# 1-Schematic_BLE_WAVER_DONGLE.net
KiCad netlist of a schematic drawn in EasyEDA
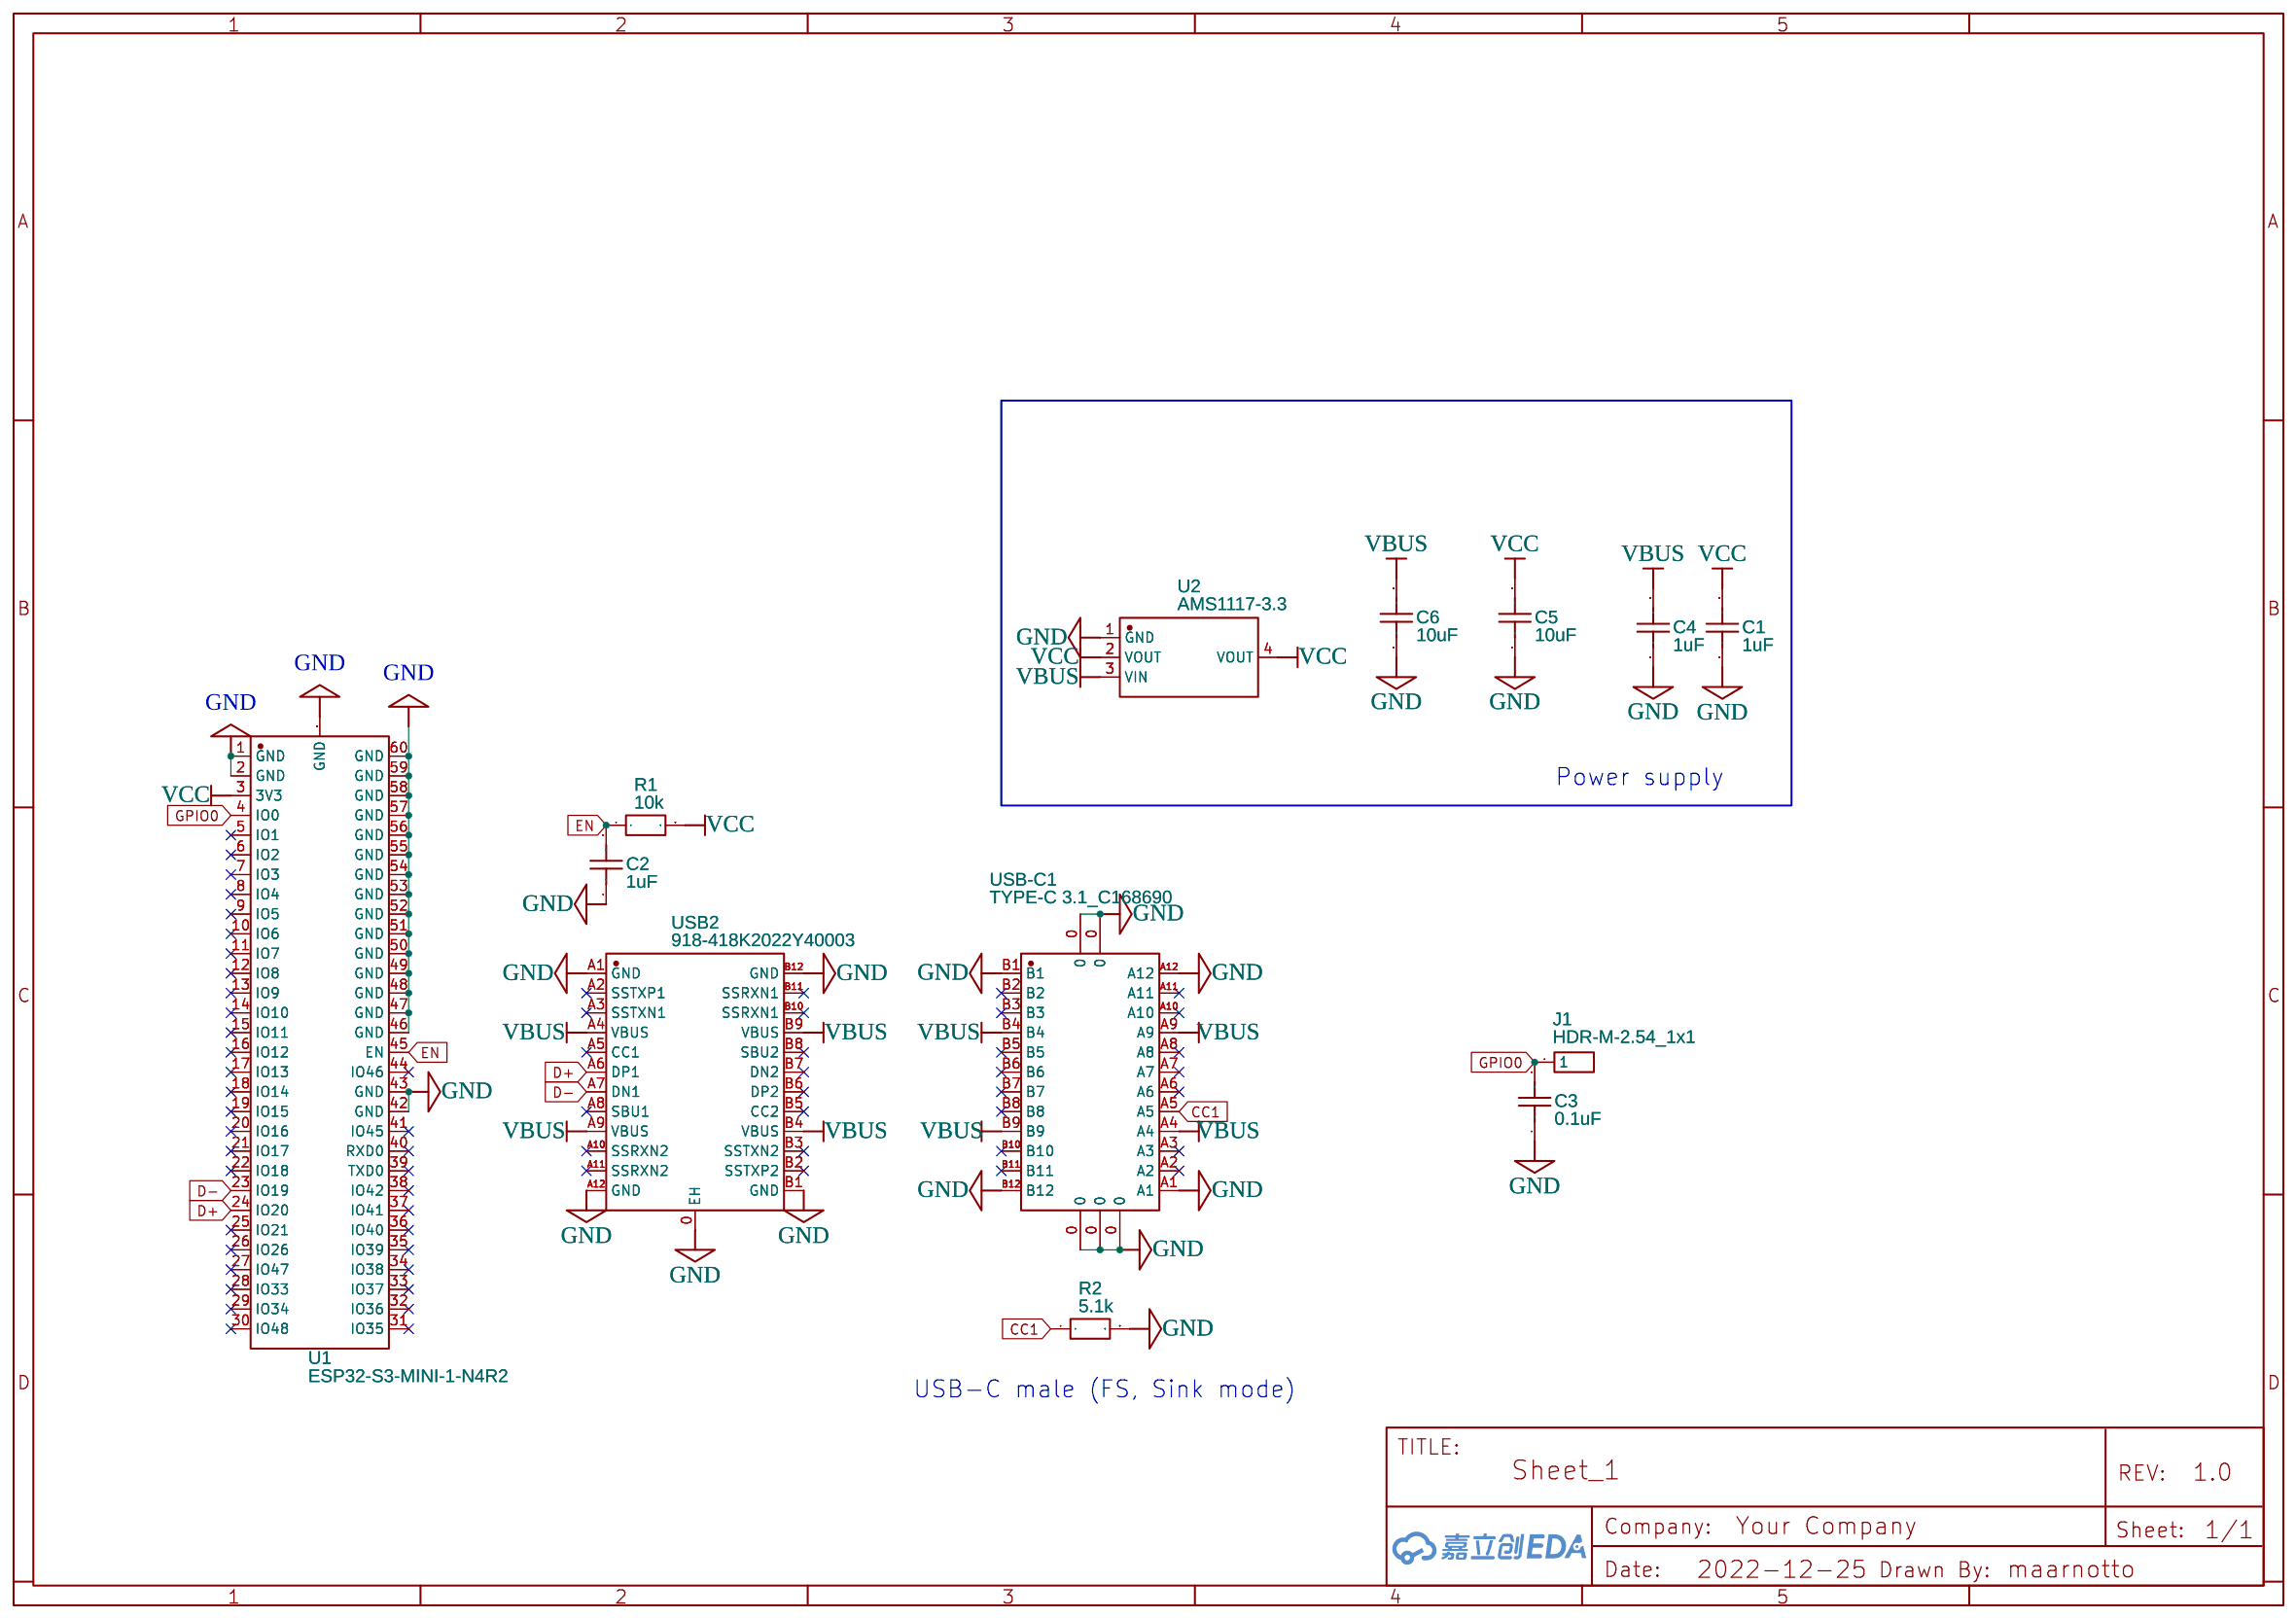
[diagram p0: schematic sheet]

(export (version "E")
  (design (tool "Eeschema 10.0.6"))
  (components
    (comp (ref "C1") (value "1uF") (libsource (lib "") (part "C_0603_US")))
    (comp (ref "C2") (value "1uF") (libsource (lib "") (part "C_0603_US")))
    (comp (ref "C3") (value "0.1uF") (libsource (lib "") (part "C_0603_US")))
    (comp (ref "C4") (value "1uF") (libsource (lib "") (part "C_0603_US")))
    (comp (ref "C5") (value "10uF") (libsource (lib "") (part "C_0603_US")))
    (comp (ref "C6") (value "10uF") (libsource (lib "") (part "C_0603_US")))
    (comp (ref "J1") (value "HDR-M-2.54_1x1") (libsource (lib "") (part "HDR-M-2.54_1x1")))
    (comp (ref "R1") (value "10k") (libsource (lib "") (part "R_0603_EU")))
    (comp (ref "R2") (value "5.1k") (libsource (lib "") (part "R_0603_EU")))
    (comp (ref "U1")
      (value "ESP32-S3-MINI-1-N4R2")
      (fields (field (name "Manufacturer") "ESPRESSIF(乐鑫)"))
      (libsource (lib "") (part "ESP32-S3-MINI-1-N4R2"))
    )
    (comp (ref "U2")
      (value "AMS1117-3.3")
      (fields (field (name "Manufacturer") "AMS"))
      (libsource (lib "") (part "AMS1117-3.3"))
    )
    (comp (ref "USB-C1")
      (value "TYPE-C 3.1_C168690")
      (fields (field (name "Manufacturer Part") "918-118A2021Y40000") (field (name "Manufacturer") "精拓金"))
      (libsource (lib "") (part "TYPE-C 3.1_C168690"))
    )
    (comp (ref "USB2")
      (value "918-418K2022Y40003")
      (fields (field (name "Manufacturer") "精拓金"))
      (libsource (lib "") (part "918-418K2022Y40003"))
    )
  )
  (nets
    (net (code "1") (name "CC1") (class "Default")
      (node (ref "R2") (pin "1") (pinfunction "1_1") (pintype "unspecified"))
      (node (ref "USB-C1") (pin "A5") (pinfunction "A5_A5") (pintype "unspecified"))
    )
    (net (code "2") (name "D+") (class "Default")
      (node (ref "U1") (pin "24") (pinfunction "IO20_24") (pintype "unspecified"))
      (node (ref "USB2") (pin "A6") (pinfunction "DP1_A6") (pintype "unspecified"))
    )
    (net (code "3") (name "D-") (class "Default")
      (node (ref "U1") (pin "23") (pinfunction "IO19_23") (pintype "unspecified"))
      (node (ref "USB2") (pin "A7") (pinfunction "DN1_A7") (pintype "unspecified"))
    )
    (net (code "4") (name "EN") (class "Default")
      (node (ref "C2") (pin "2") (pinfunction "2_2") (pintype "unspecified"))
      (node (ref "R1") (pin "1") (pinfunction "1_1") (pintype "unspecified"))
      (node (ref "U1") (pin "45") (pinfunction "EN_45") (pintype "unspecified"))
    )
    (net (code "5") (name "GND") (class "Default")
      (node (ref "C1") (pin "1") (pinfunction "1_1") (pintype "unspecified"))
      (node (ref "C2") (pin "1") (pinfunction "1_1") (pintype "unspecified"))
      (node (ref "C3") (pin "1") (pinfunction "1_1") (pintype "unspecified"))
      (node (ref "C4") (pin "1") (pinfunction "1_1") (pintype "unspecified"))
      (node (ref "C5") (pin "1") (pinfunction "1_1") (pintype "unspecified"))
      (node (ref "C6") (pin "1") (pinfunction "1_1") (pintype "unspecified"))
      (node (ref "R2") (pin "2") (pinfunction "2_2") (pintype "unspecified"))
      (node (ref "U1") (pin "1") (pinfunction "GND_1") (pintype "unspecified"))
      (node (ref "U1") (pin "2") (pinfunction "GND_2") (pintype "unspecified"))
      (node (ref "U1") (pin "42") (pinfunction "GND_42") (pintype "unspecified"))
      (node (ref "U1") (pin "43") (pinfunction "GND_43") (pintype "unspecified"))
      (node (ref "U1") (pin "46") (pinfunction "GND_46") (pintype "unspecified"))
      (node (ref "U1") (pin "47") (pinfunction "GND_47") (pintype "unspecified"))
      (node (ref "U1") (pin "48") (pinfunction "GND_48") (pintype "unspecified"))
      (node (ref "U1") (pin "49") (pinfunction "GND_49") (pintype "unspecified"))
      (node (ref "U1") (pin "50") (pinfunction "GND_50") (pintype "unspecified"))
      (node (ref "U1") (pin "51") (pinfunction "GND_51") (pintype "unspecified"))
      (node (ref "U1") (pin "52") (pinfunction "GND_52") (pintype "unspecified"))
      (node (ref "U1") (pin "53") (pinfunction "GND_53") (pintype "unspecified"))
      (node (ref "U1") (pin "54") (pinfunction "GND_54") (pintype "unspecified"))
      (node (ref "U1") (pin "55") (pinfunction "GND_55") (pintype "unspecified"))
      (node (ref "U1") (pin "56") (pinfunction "GND_56") (pintype "unspecified"))
      (node (ref "U1") (pin "57") (pinfunction "GND_57") (pintype "unspecified"))
      (node (ref "U1") (pin "58") (pinfunction "GND_58") (pintype "unspecified"))
      (node (ref "U1") (pin "59") (pinfunction "GND_59") (pintype "unspecified"))
      (node (ref "U1") (pin "60") (pinfunction "GND_60") (pintype "unspecified"))
      (node (ref "U1") (pin "GND") (pinfunction "GND_GND") (pintype "unspecified"))
      (node (ref "U2") (pin "1") (pinfunction "GND_1") (pintype "unspecified"))
      (node (ref "USB-C1") (pin "0") (pinfunction "0_0") (pintype "unspecified"))
      (node (ref "USB-C1") (pin "A1") (pinfunction "A1_A1") (pintype "unspecified"))
      (node (ref "USB-C1") (pin "A12") (pinfunction "A12_A12") (pintype "unspecified"))
      (node (ref "USB-C1") (pin "B1") (pinfunction "B1_B1") (pintype "unspecified"))
      (node (ref "USB-C1") (pin "B12") (pinfunction "B12_B12") (pintype "unspecified"))
      (node (ref "USB2") (pin "0") (pinfunction "EH_0") (pintype "unspecified"))
      (node (ref "USB2") (pin "A1") (pinfunction "GND_A1") (pintype "unspecified"))
      (node (ref "USB2") (pin "A12") (pinfunction "GND_A12") (pintype "unspecified"))
      (node (ref "USB2") (pin "B1") (pinfunction "GND_B1") (pintype "unspecified"))
      (node (ref "USB2") (pin "B12") (pinfunction "GND_B12") (pintype "unspecified"))
    )
    (net (code "6") (name "GPIO0") (class "Default")
      (node (ref "C3") (pin "2") (pinfunction "2_2") (pintype "unspecified"))
      (node (ref "J1") (pin "1") (pinfunction "1_1") (pintype "input"))
      (node (ref "U1") (pin "4") (pinfunction "IO0_4") (pintype "unspecified"))
    )
    (net (code "7") (name "VBUS") (class "Default")
      (node (ref "C4") (pin "2") (pinfunction "2_2") (pintype "unspecified"))
      (node (ref "C6") (pin "2") (pinfunction "2_2") (pintype "unspecified"))
      (node (ref "U2") (pin "3") (pinfunction "VIN_3") (pintype "unspecified"))
      (node (ref "USB-C1") (pin "A4") (pinfunction "A4_A4") (pintype "unspecified"))
      (node (ref "USB-C1") (pin "A9") (pinfunction "A9_A9") (pintype "unspecified"))
      (node (ref "USB-C1") (pin "B4") (pinfunction "B4_B4") (pintype "unspecified"))
      (node (ref "USB-C1") (pin "B9") (pinfunction "B9_B9") (pintype "unspecified"))
      (node (ref "USB2") (pin "A4") (pinfunction "VBUS_A4") (pintype "unspecified"))
      (node (ref "USB2") (pin "A9") (pinfunction "VBUS_A9") (pintype "unspecified"))
      (node (ref "USB2") (pin "B4") (pinfunction "VBUS_B4") (pintype "unspecified"))
      (node (ref "USB2") (pin "B9") (pinfunction "VBUS_B9") (pintype "unspecified"))
    )
    (net (code "8") (name "VCC") (class "Default")
      (node (ref "C1") (pin "2") (pinfunction "2_2") (pintype "unspecified"))
      (node (ref "C5") (pin "2") (pinfunction "2_2") (pintype "unspecified"))
      (node (ref "R1") (pin "2") (pinfunction "2_2") (pintype "unspecified"))
      (node (ref "U1") (pin "3") (pinfunction "3V3_3") (pintype "unspecified"))
      (node (ref "U2") (pin "2") (pinfunction "VOUT_2") (pintype "unspecified"))
      (node (ref "U2") (pin "4") (pinfunction "VOUT_4") (pintype "unspecified"))
    )
    (net (code "9") (name "unconnected-(U1-IO1-Pad5)") (class "Default")
      (node (ref "U1") (pin "5") (pinfunction "IO1_5") (pintype "unspecified+no_connect"))
    )
    (net (code "10") (name "unconnected-(U1-IO2-Pad6)") (class "Default")
      (node (ref "U1") (pin "6") (pinfunction "IO2_6") (pintype "unspecified+no_connect"))
    )
    (net (code "11") (name "unconnected-(U1-IO3-Pad7)") (class "Default")
      (node (ref "U1") (pin "7") (pinfunction "IO3_7") (pintype "unspecified+no_connect"))
    )
    (net (code "12") (name "unconnected-(U1-IO4-Pad8)") (class "Default")
      (node (ref "U1") (pin "8") (pinfunction "IO4_8") (pintype "unspecified+no_connect"))
    )
    (net (code "13") (name "unconnected-(U1-IO5-Pad9)") (class "Default")
      (node (ref "U1") (pin "9") (pinfunction "IO5_9") (pintype "unspecified+no_connect"))
    )
    (net (code "14") (name "unconnected-(U1-IO6-Pad10)") (class "Default")
      (node (ref "U1") (pin "10") (pinfunction "IO6_10") (pintype "unspecified+no_connect"))
    )
    (net (code "15") (name "unconnected-(U1-IO7-Pad11)") (class "Default")
      (node (ref "U1") (pin "11") (pinfunction "IO7_11") (pintype "unspecified+no_connect"))
    )
    (net (code "16") (name "unconnected-(U1-IO8-Pad12)") (class "Default")
      (node (ref "U1") (pin "12") (pinfunction "IO8_12") (pintype "unspecified+no_connect"))
    )
    (net (code "17") (name "unconnected-(U1-IO9-Pad13)") (class "Default")
      (node (ref "U1") (pin "13") (pinfunction "IO9_13") (pintype "unspecified+no_connect"))
    )
    (net (code "18") (name "unconnected-(U1-IO10-Pad14)") (class "Default")
      (node (ref "U1") (pin "14") (pinfunction "IO10_14") (pintype "unspecified+no_connect"))
    )
    (net (code "19") (name "unconnected-(U1-IO11-Pad15)") (class "Default")
      (node (ref "U1") (pin "15") (pinfunction "IO11_15") (pintype "unspecified+no_connect"))
    )
    (net (code "20") (name "unconnected-(U1-IO12-Pad16)") (class "Default")
      (node (ref "U1") (pin "16") (pinfunction "IO12_16") (pintype "unspecified+no_connect"))
    )
    (net (code "21") (name "unconnected-(U1-IO13-Pad17)") (class "Default")
      (node (ref "U1") (pin "17") (pinfunction "IO13_17") (pintype "unspecified+no_connect"))
    )
    (net (code "22") (name "unconnected-(U1-IO14-Pad18)") (class "Default")
      (node (ref "U1") (pin "18") (pinfunction "IO14_18") (pintype "unspecified+no_connect"))
    )
    (net (code "23") (name "unconnected-(U1-IO15-Pad19)") (class "Default")
      (node (ref "U1") (pin "19") (pinfunction "IO15_19") (pintype "unspecified+no_connect"))
    )
    (net (code "24") (name "unconnected-(U1-IO16-Pad20)") (class "Default")
      (node (ref "U1") (pin "20") (pinfunction "IO16_20") (pintype "unspecified+no_connect"))
    )
    (net (code "25") (name "unconnected-(U1-IO17-Pad21)") (class "Default")
      (node (ref "U1") (pin "21") (pinfunction "IO17_21") (pintype "unspecified+no_connect"))
    )
    (net (code "26") (name "unconnected-(U1-IO18-Pad22)") (class "Default")
      (node (ref "U1") (pin "22") (pinfunction "IO18_22") (pintype "unspecified+no_connect"))
    )
    (net (code "27") (name "unconnected-(U1-IO21-Pad25)") (class "Default")
      (node (ref "U1") (pin "25") (pinfunction "IO21_25") (pintype "unspecified+no_connect"))
    )
    (net (code "28") (name "unconnected-(U1-IO26-Pad26)") (class "Default")
      (node (ref "U1") (pin "26") (pinfunction "IO26_26") (pintype "unspecified+no_connect"))
    )
    (net (code "29") (name "unconnected-(U1-IO33-Pad28)") (class "Default")
      (node (ref "U1") (pin "28") (pinfunction "IO33_28") (pintype "unspecified+no_connect"))
    )
    (net (code "30") (name "unconnected-(U1-IO34-Pad29)") (class "Default")
      (node (ref "U1") (pin "29") (pinfunction "IO34_29") (pintype "unspecified+no_connect"))
    )
    (net (code "31") (name "unconnected-(U1-IO35-Pad31)") (class "Default")
      (node (ref "U1") (pin "31") (pinfunction "IO35_31") (pintype "unspecified+no_connect"))
    )
    (net (code "32") (name "unconnected-(U1-IO36-Pad32)") (class "Default")
      (node (ref "U1") (pin "32") (pinfunction "IO36_32") (pintype "unspecified+no_connect"))
    )
    (net (code "33") (name "unconnected-(U1-IO37-Pad33)") (class "Default")
      (node (ref "U1") (pin "33") (pinfunction "IO37_33") (pintype "unspecified+no_connect"))
    )
    (net (code "34") (name "unconnected-(U1-IO38-Pad34)") (class "Default")
      (node (ref "U1") (pin "34") (pinfunction "IO38_34") (pintype "unspecified+no_connect"))
    )
    (net (code "35") (name "unconnected-(U1-IO39-Pad35)") (class "Default")
      (node (ref "U1") (pin "35") (pinfunction "IO39_35") (pintype "unspecified+no_connect"))
    )
    (net (code "36") (name "unconnected-(U1-IO40-Pad36)") (class "Default")
      (node (ref "U1") (pin "36") (pinfunction "IO40_36") (pintype "unspecified+no_connect"))
    )
    (net (code "37") (name "unconnected-(U1-IO41-Pad37)") (class "Default")
      (node (ref "U1") (pin "37") (pinfunction "IO41_37") (pintype "unspecified+no_connect"))
    )
    (net (code "38") (name "unconnected-(U1-IO42-Pad38)") (class "Default")
      (node (ref "U1") (pin "38") (pinfunction "IO42_38") (pintype "unspecified+no_connect"))
    )
    (net (code "39") (name "unconnected-(U1-IO45-Pad41)") (class "Default")
      (node (ref "U1") (pin "41") (pinfunction "IO45_41") (pintype "unspecified+no_connect"))
    )
    (net (code "40") (name "unconnected-(U1-IO46-Pad44)") (class "Default")
      (node (ref "U1") (pin "44") (pinfunction "IO46_44") (pintype "unspecified+no_connect"))
    )
    (net (code "41") (name "unconnected-(U1-IO47-Pad27)") (class "Default")
      (node (ref "U1") (pin "27") (pinfunction "IO47_27") (pintype "unspecified+no_connect"))
    )
    (net (code "42") (name "unconnected-(U1-IO48-Pad30)") (class "Default")
      (node (ref "U1") (pin "30") (pinfunction "IO48_30") (pintype "unspecified+no_connect"))
    )
    (net (code "43") (name "unconnected-(U1-RXD0-Pad40)") (class "Default")
      (node (ref "U1") (pin "40") (pinfunction "RXD0_40") (pintype "unspecified+no_connect"))
    )
    (net (code "44") (name "unconnected-(U1-TXD0-Pad39)") (class "Default")
      (node (ref "U1") (pin "39") (pinfunction "TXD0_39") (pintype "unspecified+no_connect"))
    )
    (net (code "45") (name "unconnected-(USB-C1-PadA2)") (class "Default")
      (node (ref "USB-C1") (pin "A2") (pinfunction "A2_A2") (pintype "unspecified+no_connect"))
    )
    (net (code "46") (name "unconnected-(USB-C1-PadA3)") (class "Default")
      (node (ref "USB-C1") (pin "A3") (pinfunction "A3_A3") (pintype "unspecified+no_connect"))
    )
    (net (code "47") (name "unconnected-(USB-C1-PadA6)") (class "Default")
      (node (ref "USB-C1") (pin "A6") (pinfunction "A6_A6") (pintype "unspecified+no_connect"))
    )
    (net (code "48") (name "unconnected-(USB-C1-PadA7)") (class "Default")
      (node (ref "USB-C1") (pin "A7") (pinfunction "A7_A7") (pintype "unspecified+no_connect"))
    )
    (net (code "49") (name "unconnected-(USB-C1-PadA8)") (class "Default")
      (node (ref "USB-C1") (pin "A8") (pinfunction "A8_A8") (pintype "unspecified+no_connect"))
    )
    (net (code "50") (name "unconnected-(USB-C1-PadA10)") (class "Default")
      (node (ref "USB-C1") (pin "A10") (pinfunction "A10_A10") (pintype "unspecified+no_connect"))
    )
    (net (code "51") (name "unconnected-(USB-C1-PadA11)") (class "Default")
      (node (ref "USB-C1") (pin "A11") (pinfunction "A11_A11") (pintype "unspecified+no_connect"))
    )
    (net (code "52") (name "unconnected-(USB-C1-PadB2)") (class "Default")
      (node (ref "USB-C1") (pin "B2") (pinfunction "B2_B2") (pintype "unspecified+no_connect"))
    )
    (net (code "53") (name "unconnected-(USB-C1-PadB3)") (class "Default")
      (node (ref "USB-C1") (pin "B3") (pinfunction "B3_B3") (pintype "unspecified+no_connect"))
    )
    (net (code "54") (name "unconnected-(USB-C1-PadB5)") (class "Default")
      (node (ref "USB-C1") (pin "B5") (pinfunction "B5_B5") (pintype "unspecified+no_connect"))
    )
    (net (code "55") (name "unconnected-(USB-C1-PadB6)") (class "Default")
      (node (ref "USB-C1") (pin "B6") (pinfunction "B6_B6") (pintype "unspecified+no_connect"))
    )
    (net (code "56") (name "unconnected-(USB-C1-PadB7)") (class "Default")
      (node (ref "USB-C1") (pin "B7") (pinfunction "B7_B7") (pintype "unspecified+no_connect"))
    )
    (net (code "57") (name "unconnected-(USB-C1-PadB8)") (class "Default")
      (node (ref "USB-C1") (pin "B8") (pinfunction "B8_B8") (pintype "unspecified+no_connect"))
    )
    (net (code "58") (name "unconnected-(USB-C1-PadB10)") (class "Default")
      (node (ref "USB-C1") (pin "B10") (pinfunction "B10_B10") (pintype "unspecified+no_connect"))
    )
    (net (code "59") (name "unconnected-(USB-C1-PadB11)") (class "Default")
      (node (ref "USB-C1") (pin "B11") (pinfunction "B11_B11") (pintype "unspecified+no_connect"))
    )
    (net (code "60") (name "unconnected-(USB2-CC1-PadA5)") (class "Default")
      (node (ref "USB2") (pin "A5") (pinfunction "CC1_A5") (pintype "unspecified+no_connect"))
    )
    (net (code "61") (name "unconnected-(USB2-CC2-PadB5)") (class "Default")
      (node (ref "USB2") (pin "B5") (pinfunction "CC2_B5") (pintype "unspecified+no_connect"))
    )
    (net (code "62") (name "unconnected-(USB2-DN2-PadB7)") (class "Default")
      (node (ref "USB2") (pin "B7") (pinfunction "DN2_B7") (pintype "unspecified+no_connect"))
    )
    (net (code "63") (name "unconnected-(USB2-DP2-PadB6)") (class "Default")
      (node (ref "USB2") (pin "B6") (pinfunction "DP2_B6") (pintype "unspecified+no_connect"))
    )
    (net (code "64") (name "unconnected-(USB2-SBU1-PadA8)") (class "Default")
      (node (ref "USB2") (pin "A8") (pinfunction "SBU1_A8") (pintype "unspecified+no_connect"))
    )
    (net (code "65") (name "unconnected-(USB2-SBU2-PadB8)") (class "Default")
      (node (ref "USB2") (pin "B8") (pinfunction "SBU2_B8") (pintype "unspecified+no_connect"))
    )
    (net (code "66") (name "unconnected-(USB2-SSRXN1-PadB10)") (class "Default")
      (node (ref "USB2") (pin "B10") (pinfunction "SSRXN1_B10") (pintype "unspecified+no_connect"))
    )
    (net (code "67") (name "unconnected-(USB2-SSRXN1-PadB11)") (class "Default")
      (node (ref "USB2") (pin "B11") (pinfunction "SSRXN1_B11") (pintype "unspecified+no_connect"))
    )
    (net (code "68") (name "unconnected-(USB2-SSRXN2-PadA10)") (class "Default")
      (node (ref "USB2") (pin "A10") (pinfunction "SSRXN2_A10") (pintype "unspecified+no_connect"))
    )
    (net (code "69") (name "unconnected-(USB2-SSRXN2-PadA11)") (class "Default")
      (node (ref "USB2") (pin "A11") (pinfunction "SSRXN2_A11") (pintype "unspecified+no_connect"))
    )
    (net (code "70") (name "unconnected-(USB2-SSTXN1-PadA3)") (class "Default")
      (node (ref "USB2") (pin "A3") (pinfunction "SSTXN1_A3") (pintype "unspecified+no_connect"))
    )
    (net (code "71") (name "unconnected-(USB2-SSTXN2-PadB3)") (class "Default")
      (node (ref "USB2") (pin "B3") (pinfunction "SSTXN2_B3") (pintype "unspecified+no_connect"))
    )
    (net (code "72") (name "unconnected-(USB2-SSTXP1-PadA2)") (class "Default")
      (node (ref "USB2") (pin "A2") (pinfunction "SSTXP1_A2") (pintype "unspecified+no_connect"))
    )
    (net (code "73") (name "unconnected-(USB2-SSTXP2-PadB2)") (class "Default")
      (node (ref "USB2") (pin "B2") (pinfunction "SSTXP2_B2") (pintype "unspecified+no_connect"))
    )
  )
)
